# design.net
KiCad netlist of a schematic drawn in Altium Designer
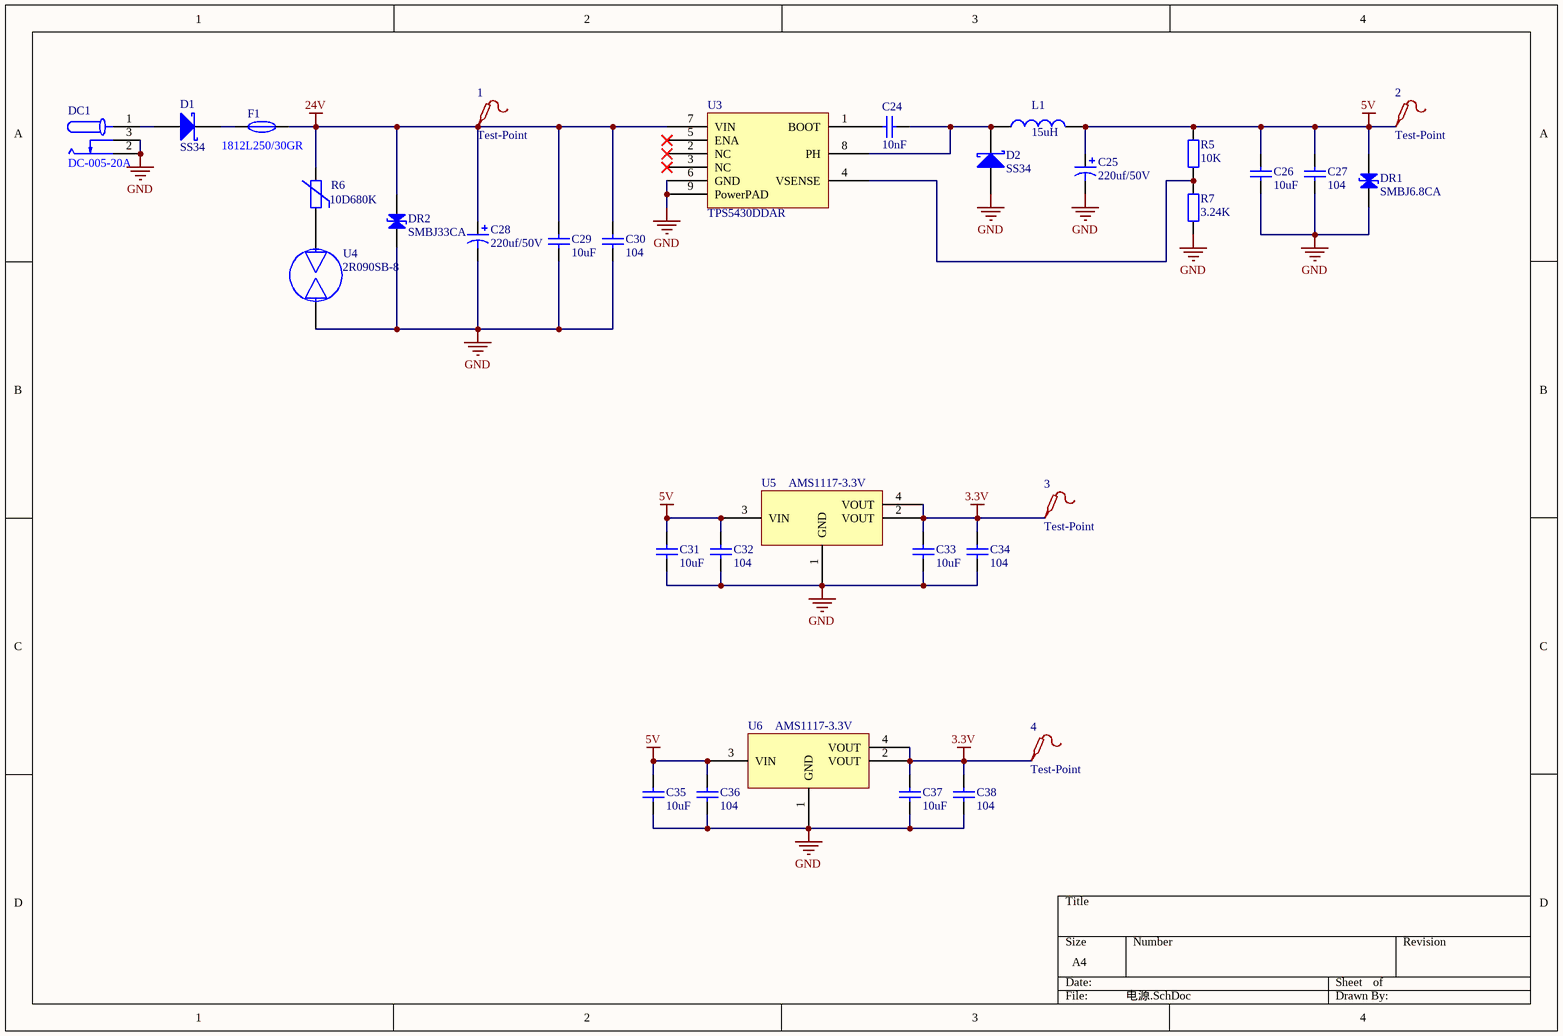
[diagram p0: 电源.SchDoc]

(export (version "E")
  (design (tool "Eeschema 10.0.6"))
  (components
    (comp (ref "1")
      (value "Test-Point")
      (footprint "Test-Point-0.5mm")
      (libsource (lib "STM32_PLC_20251215") (part "Test-Point"))
    )
    (comp (ref "2")
      (value "Test-Point")
      (footprint "Test-Point-0.5mm")
      (libsource (lib "STM32_PLC_20251215") (part "Test-Point"))
    )
    (comp (ref "3")
      (value "Test-Point")
      (footprint "Test-Point-0.5mm")
      (libsource (lib "STM32_PLC_20251215") (part "Test-Point"))
    )
    (comp (ref "4")
      (value "Test-Point")
      (footprint "Test-Point-0.5mm")
      (libsource (lib "STM32_PLC_20251215") (part "Test-Point"))
    )
    (comp (ref "C24")
      (value "10nF")
      (footprint "C 0603_L")
      (description "0603贴片电容")
      (fields (field (name "PUBLISHER") "Altium Limited"))
      (libsource (lib "STM32_PLC_20251215") (part "Cap"))
    )
    (comp (ref "C25")
      (value "220uf/50V")
      (footprint "CAP 2.5*6.3*11.2 - GD")
      (description "Polarized Capacitor (Radial)")
      (fields (field (name "PUBLISHER") "Altium Limited"))
      (libsource (lib "红外能量舱") (part "Cap Pol1"))
    )
    (comp (ref "C26")
      (value "10uF")
      (footprint "C 0603_L")
      (description "0603贴片电容")
      (fields (field (name "PUBLISHER") "Altium Limited"))
      (libsource (lib "STM32_PLC_20251215") (part "Cap"))
    )
    (comp (ref "C27")
      (value "104")
      (footprint "C 0603_L")
      (description "0603贴片电容")
      (fields (field (name "PUBLISHER") "Altium Limited"))
      (libsource (lib "STM32_PLC_20251215") (part "Cap"))
    )
    (comp (ref "C28")
      (value "220uf/50V")
      (footprint "CAP 2.5*6.3*11.2 - GD")
      (description "Polarized Capacitor (Radial)")
      (fields (field (name "PUBLISHER") "Altium Limited"))
      (libsource (lib "红外能量舱") (part "Cap Pol1"))
    )
    (comp (ref "C29")
      (value "10uF")
      (footprint "C 0603_L")
      (description "0603贴片电容")
      (fields (field (name "PUBLISHER") "Altium Limited"))
      (libsource (lib "STM32_PLC_20251215") (part "Cap"))
    )
    (comp (ref "C30")
      (value "104")
      (footprint "C 0603_L")
      (description "0603贴片电容")
      (fields (field (name "PUBLISHER") "Altium Limited"))
      (libsource (lib "STM32_PLC_20251215") (part "Cap"))
    )
    (comp (ref "C31")
      (value "10uF")
      (footprint "C 0603_L")
      (description "0603贴片电容")
      (fields (field (name "PUBLISHER") "Altium Limited"))
      (libsource (lib "STM32_PLC_20251215") (part "Cap"))
    )
    (comp (ref "C32")
      (value "104")
      (footprint "C 0603_L")
      (description "0603贴片电容")
      (fields (field (name "PUBLISHER") "Altium Limited"))
      (libsource (lib "STM32_PLC_20251215") (part "Cap"))
    )
    (comp (ref "C33")
      (value "10uF")
      (footprint "C 0603_L")
      (description "0603贴片电容")
      (fields (field (name "PUBLISHER") "Altium Limited"))
      (libsource (lib "STM32_PLC_20251215") (part "Cap"))
    )
    (comp (ref "C34")
      (value "104")
      (footprint "C 0603_L")
      (description "0603贴片电容")
      (fields (field (name "PUBLISHER") "Altium Limited"))
      (libsource (lib "STM32_PLC_20251215") (part "Cap"))
    )
    (comp (ref "C35")
      (value "10uF")
      (footprint "C 0603_L")
      (description "0603贴片电容")
      (fields (field (name "PUBLISHER") "Altium Limited"))
      (libsource (lib "STM32_PLC_20251215") (part "Cap"))
    )
    (comp (ref "C36")
      (value "104")
      (footprint "C 0603_L")
      (description "0603贴片电容")
      (fields (field (name "PUBLISHER") "Altium Limited"))
      (libsource (lib "STM32_PLC_20251215") (part "Cap"))
    )
    (comp (ref "C37")
      (value "10uF")
      (footprint "C 0603_L")
      (description "0603贴片电容")
      (fields (field (name "PUBLISHER") "Altium Limited"))
      (libsource (lib "STM32_PLC_20251215") (part "Cap"))
    )
    (comp (ref "C38")
      (value "104")
      (footprint "C 0603_L")
      (description "0603贴片电容")
      (fields (field (name "PUBLISHER") "Altium Limited"))
      (libsource (lib "STM32_PLC_20251215") (part "Cap"))
    )
    (comp (ref "D1")
      (value "SS34")
      (footprint "SMA")
      (description "SMA肖特基二极管")
      (libsource (lib "STM32_PLC_20251215") (part "SS34"))
    )
    (comp (ref "D2")
      (value "SS34")
      (footprint "SMA")
      (description "SMA肖特基二极管")
      (libsource (lib "STM32_PLC_20251215") (part "B340A"))
    )
    (comp (ref "DC1")
      (value "DC-005-20A")
      (footprint "DC-005")
      (description "DC电源接口")
      (fields (field (name "MANUFACTURER") "韩国韩荣"))
      (libsource (lib "STM32_PLC_20251215") (part "DC-005-20A"))
    )
    (comp (ref "DR1")
      (value "SMBJ6.8CA")
      (footprint "SMB")
      (description "DO-214AA，瞬态电压抑制二极管")
      (fields (field (name "版权归属") "源创客"))
      (libsource (lib "STM32_PLC_20251215") (part "TVS"))
    )
    (comp (ref "DR2")
      (value "SMBJ33CA")
      (footprint "SMB")
      (description "DO-214AA，瞬态电压抑制二极管")
      (fields (field (name "版权归属") "源创客"))
      (libsource (lib "STM32_PLC_20251215") (part "TVS"))
    )
    (comp (ref "F1")
      (value "1812L250/30GR")
      (footprint "F1812")
      (description "1812，自恢复保险丝")
      (fields (field (name "MANUFACTURER") "LUTE(陆特)"))
      (libsource (lib "STM32_PLC_20251215") (part "1812L250/30GR"))
    )
    (comp (ref "L1")
      (value "15uH")
      (footprint "IND-SMD_L7.0-W6.6_FXL0630")
      (description "15uH小功率贴片电感")
      (fields (field (name "版权归属") "源创客"))
      (libsource (lib "STM32_PLC_20251215") (part "L"))
    )
    (comp (ref "R5")
      (value "10K")
      (footprint "R 0603_L")
      (description "C0603贴片电阻")
      (fields (field (name "版权归属") "源创客"))
      (libsource (lib "STM32_PLC_20251215") (part "Res"))
    )
    (comp (ref "R6")
      (value "10D680K")
      (footprint "RES-TH_L12.0-W4.5-P7.50-D0.8-S1.60")
      (description "压敏电阻")
      (fields (field (name "版权归属") "源创客"))
      (libsource (lib "STM32F407_PLC_20260104_") (part "R_VDR"))
    )
    (comp (ref "R7")
      (value "3.24K")
      (footprint "R 0603_L")
      (description "C0603贴片电阻")
      (fields (field (name "版权归属") "源创客"))
      (libsource (lib "STM32_PLC_20251215") (part "Res"))
    )
    (comp (ref "U3")
      (value "TPS5430DDAR")
      (footprint "tps5430")
      (description "DC-DC，SOIC-8-EP")
      (fields (field (name "MANUFACTURER") "TI(德州仪器)") (field (name "NAME") "TPS5430DDAR"))
      (libsource (lib "STM32_PLC_20251215") (part "TPS5430DDAR"))
    )
    (comp (ref "U4")
      (value "2R090SB-8")
      (footprint "DIO-DT-SMD_L8.0-W6.0")
      (description "气体放电管，90V、10kA")
      (fields (field (name "MANUFACTURER") "RUILON(瑞隆源)") (field (name "TOLERANCE") "±20%"))
      (libsource (lib "STM32F407_PLC_20260104_") (part "2R090SB-8_C485316"))
    )
    (comp (ref "U5")
      (value "AMS1117-3.3V")
      (footprint "SOT-223-3_L6.5-W3.4-P2.30-LS7.0-BR")
      (description "线性稳压器")
      (libsource (lib "STM32_PLC_20251215") (part "AMS1117-3.3V"))
    )
    (comp (ref "U6")
      (value "AMS1117-3.3V")
      (footprint "SOT-223-3_L6.5-W3.4-P2.30-LS7.0-BR")
      (description "线性稳压器")
      (libsource (lib "STM32_PLC_20251215") (part "AMS1117-3.3V"))
    )
  )
  (nets
    (net (code "1") (name "3.3V") (class "Default")
      (node (ref "3") (pin "1") (pinfunction "1_1") (pintype "passive"))
      (node (ref "4") (pin "1") (pinfunction "1_1") (pintype "passive"))
      (node (ref "C33") (pin "2") (pinfunction "2_2") (pintype "passive"))
      (node (ref "C34") (pin "2") (pinfunction "2_2") (pintype "passive"))
      (node (ref "C37") (pin "2") (pinfunction "2_2") (pintype "passive"))
      (node (ref "C38") (pin "2") (pinfunction "2_2") (pintype "passive"))
      (node (ref "U5") (pin "2") (pinfunction "VOUT_2") (pintype "passive"))
      (node (ref "U5") (pin "4") (pinfunction "VOUT_4") (pintype "passive"))
      (node (ref "U6") (pin "2") (pinfunction "VOUT_2") (pintype "passive"))
      (node (ref "U6") (pin "4") (pinfunction "VOUT_4") (pintype "passive"))
    )
    (net (code "2") (name "5V") (class "Default")
      (node (ref "2") (pin "1") (pinfunction "1_1") (pintype "passive"))
      (node (ref "C25") (pin "1") (pinfunction "1_1") (pintype "passive"))
      (node (ref "C26") (pin "2") (pinfunction "2_2") (pintype "passive"))
      (node (ref "C27") (pin "2") (pinfunction "2_2") (pintype "passive"))
      (node (ref "C31") (pin "2") (pinfunction "2_2") (pintype "passive"))
      (node (ref "C32") (pin "2") (pinfunction "2_2") (pintype "passive"))
      (node (ref "C35") (pin "2") (pinfunction "2_2") (pintype "passive"))
      (node (ref "C36") (pin "2") (pinfunction "2_2") (pintype "passive"))
      (node (ref "DR1") (pin "1") (pinfunction "A_1") (pintype "passive"))
      (node (ref "L1") (pin "2") (pinfunction "2_2") (pintype "passive"))
      (node (ref "R5") (pin "2") (pinfunction "2_2") (pintype "passive"))
      (node (ref "U5") (pin "3") (pinfunction "VIN_3") (pintype "passive"))
      (node (ref "U6") (pin "3") (pinfunction "VIN_3") (pintype "passive"))
    )
    (net (code "3") (name "24V") (class "Default")
      (node (ref "1") (pin "1") (pinfunction "1_1") (pintype "passive"))
      (node (ref "C28") (pin "1") (pinfunction "1_1") (pintype "passive"))
      (node (ref "C29") (pin "2") (pinfunction "2_2") (pintype "passive"))
      (node (ref "C30") (pin "2") (pinfunction "2_2") (pintype "passive"))
      (node (ref "DR2") (pin "1") (pinfunction "A_1") (pintype "passive"))
      (node (ref "F1") (pin "2") (pinfunction "2_2") (pintype "passive"))
      (node (ref "R6") (pin "2") (pinfunction "2_2") (pintype "passive"))
      (node (ref "U3") (pin "7") (pinfunction "VIN_7") (pintype "passive"))
    )
    (net (code "4") (name "GND") (class "Default")
      (node (ref "C25") (pin "2") (pinfunction "2_2") (pintype "passive"))
      (node (ref "C26") (pin "1") (pinfunction "1_1") (pintype "passive"))
      (node (ref "C27") (pin "1") (pinfunction "1_1") (pintype "passive"))
      (node (ref "C28") (pin "2") (pinfunction "2_2") (pintype "passive"))
      (node (ref "C29") (pin "1") (pinfunction "1_1") (pintype "passive"))
      (node (ref "C30") (pin "1") (pinfunction "1_1") (pintype "passive"))
      (node (ref "C31") (pin "1") (pinfunction "1_1") (pintype "passive"))
      (node (ref "C32") (pin "1") (pinfunction "1_1") (pintype "passive"))
      (node (ref "C33") (pin "1") (pinfunction "1_1") (pintype "passive"))
      (node (ref "C34") (pin "1") (pinfunction "1_1") (pintype "passive"))
      (node (ref "C35") (pin "1") (pinfunction "1_1") (pintype "passive"))
      (node (ref "C36") (pin "1") (pinfunction "1_1") (pintype "passive"))
      (node (ref "C37") (pin "1") (pinfunction "1_1") (pintype "passive"))
      (node (ref "C38") (pin "1") (pinfunction "1_1") (pintype "passive"))
      (node (ref "D2") (pin "1") (pinfunction "A_1") (pintype "passive"))
      (node (ref "DC1") (pin "2") (pinfunction "2_2") (pintype "passive"))
      (node (ref "DC1") (pin "3") (pinfunction "3_3") (pintype "passive"))
      (node (ref "DR1") (pin "2") (pinfunction "K_2") (pintype "passive"))
      (node (ref "DR2") (pin "2") (pinfunction "K_2") (pintype "passive"))
      (node (ref "R7") (pin "1") (pinfunction "1_1") (pintype "passive"))
      (node (ref "U3") (pin "6") (pinfunction "GND_6") (pintype "passive"))
      (node (ref "U3") (pin "9") (pinfunction "PowerPAD_9") (pintype "passive"))
      (node (ref "U4") (pin "2") (pinfunction "2_2") (pintype "passive"))
      (node (ref "U5") (pin "1") (pinfunction "GND_1") (pintype "passive"))
      (node (ref "U6") (pin "1") (pinfunction "GND_1") (pintype "passive"))
    )
    (net (code "5") (name "Net-(D1-A)") (class "Default")
      (node (ref "D1") (pin "1") (pinfunction "A_1") (pintype "passive"))
      (node (ref "DC1") (pin "1") (pinfunction "1_1") (pintype "passive"))
    )
    (net (code "6") (name "Net-(D1-K)") (class "Default")
      (node (ref "D1") (pin "2") (pinfunction "K_2") (pintype "passive"))
      (node (ref "F1") (pin "1") (pinfunction "1_1") (pintype "passive"))
    )
    (net (code "7") (name "Net-(D2-K)") (class "Default")
      (node (ref "C24") (pin "1") (pinfunction "1_1") (pintype "passive"))
      (node (ref "D2") (pin "2") (pinfunction "K_2") (pintype "passive"))
      (node (ref "L1") (pin "1") (pinfunction "1_1") (pintype "passive"))
      (node (ref "U3") (pin "8") (pinfunction "PH_8") (pintype "passive"))
    )
    (net (code "8") (name "Net-(R6-Pad1)") (class "Default")
      (node (ref "R6") (pin "1") (pinfunction "1_1") (pintype "passive"))
      (node (ref "U4") (pin "1") (pinfunction "1_1") (pintype "passive"))
    )
    (net (code "9") (name "Net-(U3-BOOT)") (class "Default")
      (node (ref "C24") (pin "2") (pinfunction "2_2") (pintype "passive"))
      (node (ref "U3") (pin "1") (pinfunction "BOOT_1") (pintype "passive"))
    )
    (net (code "10") (name "Net-(U3-VSENSE)") (class "Default")
      (node (ref "R5") (pin "1") (pinfunction "1_1") (pintype "passive"))
      (node (ref "R7") (pin "2") (pinfunction "2_2") (pintype "passive"))
      (node (ref "U3") (pin "4") (pinfunction "VSENSE_4") (pintype "passive"))
    )
    (net (code "11") (name "unconnected-(U3-ENA-Pad5)") (class "Default")
      (node (ref "U3") (pin "5") (pinfunction "ENA_5") (pintype "passive+no_connect"))
    )
    (net (code "12") (name "unconnected-(U3-NC-Pad2)") (class "Default")
      (node (ref "U3") (pin "2") (pinfunction "NC_2") (pintype "passive+no_connect"))
    )
    (net (code "13") (name "unconnected-(U3-NC-Pad3)") (class "Default")
      (node (ref "U3") (pin "3") (pinfunction "NC_3") (pintype "passive+no_connect"))
    )
  )
)
